# max9611.net
KiCad netlist of a schematic drawn in EAGLE
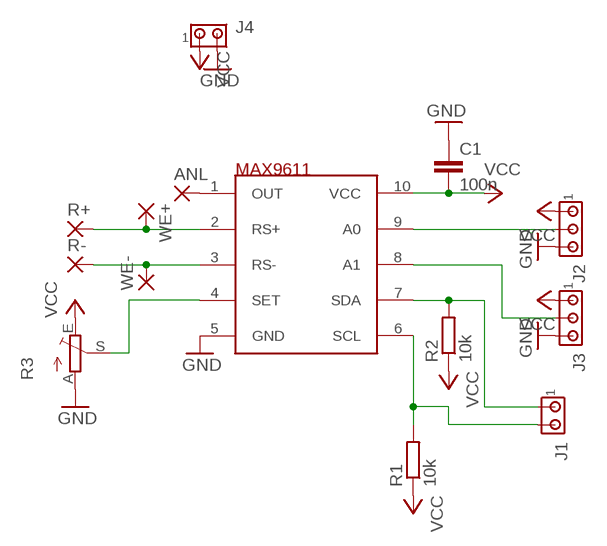
[diagram p0: schematic, sheet 1]

(export (version "E")
  (design (tool "Eeschema 10.0.6"))
  (components
    (comp (ref "ANL")
      (value "1,6/0,8")
      (footprint "eagle-import:1,6_0,8")
      (libsource (lib "eagle-import") (part "1,6/0,8"))
    )
    (comp (ref "C1")
      (value "100n")
      (footprint "eagle-import:C0805")
      (libsource (lib "eagle-import") (part "C-EUC0805"))
    )
    (comp (ref "J1")
      (value "MTA02-100")
      (footprint "eagle-import:10X02MTA")
      (libsource (lib "eagle-import") (part "MTA02-100"))
    )
    (comp (ref "J2")
      (value "MTA03-100")
      (footprint "eagle-import:10X03MTA")
      (libsource (lib "eagle-import") (part "MTA03-100"))
    )
    (comp (ref "J3")
      (value "MTA03-100")
      (footprint "eagle-import:10X03MTA")
      (libsource (lib "eagle-import") (part "MTA03-100"))
    )
    (comp (ref "J4")
      (value "MTA02-100")
      (footprint "eagle-import:10X02MTA")
      (libsource (lib "eagle-import") (part "MTA02-100"))
    )
    (comp (ref "R+")
      (value "1,6/0,8")
      (footprint "eagle-import:1,6_0,8")
      (libsource (lib "eagle-import") (part "1,6/0,8"))
    )
    (comp (ref "R-")
      (value "1,6/0,8")
      (footprint "eagle-import:1,6_0,8")
      (libsource (lib "eagle-import") (part "1,6/0,8"))
    )
    (comp (ref "R1")
      (value "10k")
      (footprint "eagle-import:M0805")
      (libsource (lib "eagle-import") (part "R-EU_M0805"))
    )
    (comp (ref "R2")
      (value "10k")
      (footprint "eagle-import:M0805")
      (libsource (lib "eagle-import") (part "R-EU_M0805"))
    )
    (comp (ref "R3")
      (value "TRIM_EU-RJ9W")
      (footprint "eagle-import:RJ9W")
      (libsource (lib "eagle-import") (part "TRIM_EU-RJ9W"))
    )
    (comp (ref "U$1")
      (value "MAX9611")
      (footprint "eagle-import:UMAX10")
      (libsource (lib "eagle-import") (part "MAX9611"))
    )
    (comp (ref "WE+")
      (value "1,6/0,8")
      (footprint "eagle-import:1,6_0,8")
      (libsource (lib "eagle-import") (part "1,6/0,8"))
    )
    (comp (ref "WE-")
      (value "1,6/0,8")
      (footprint "eagle-import:1,6_0,8")
      (libsource (lib "eagle-import") (part "1,6/0,8"))
    )
  )
  (nets
    (net (code "1") (name "GND") (class "Default")
      (node (ref "C1") (pin "1") (pinfunction "1_1") (pintype "passive"))
      (node (ref "J2") (pin "3") (pinfunction "3_3") (pintype "passive"))
      (node (ref "J3") (pin "3") (pinfunction "3_3") (pintype "passive"))
      (node (ref "J4") (pin "2") (pinfunction "2_2") (pintype "passive"))
      (node (ref "R3") (pin "A") (pinfunction "A_A") (pintype "passive"))
      (node (ref "U$1") (pin "5") (pinfunction "GND_5") (pintype "bidirectional"))
    )
    (net (code "2") (name "Net-(ANL-P)") (class "Default")
      (node (ref "ANL") (pin "1") (pinfunction "P_1") (pintype "passive"))
      (node (ref "U$1") (pin "1") (pinfunction "OUT_1") (pintype "bidirectional"))
    )
    (net (code "3") (name "Net-(R+-P)") (class "Default")
      (node (ref "R+") (pin "1") (pinfunction "P_1") (pintype "passive"))
      (node (ref "U$1") (pin "2") (pinfunction "RS+_2") (pintype "bidirectional"))
      (node (ref "WE+") (pin "1") (pinfunction "P_1") (pintype "passive"))
    )
    (net (code "4") (name "Net-(R--P)") (class "Default")
      (node (ref "R-") (pin "1") (pinfunction "P_1") (pintype "passive"))
      (node (ref "U$1") (pin "3") (pinfunction "RS-_3") (pintype "bidirectional"))
      (node (ref "WE-") (pin "1") (pinfunction "P_1") (pintype "passive"))
    )
    (net (code "5") (name "Net-(U$1-A0)") (class "Default")
      (node (ref "J2") (pin "2") (pinfunction "2_2") (pintype "passive"))
      (node (ref "U$1") (pin "9") (pinfunction "A0_9") (pintype "bidirectional"))
    )
    (net (code "6") (name "Net-(U$1-A1)") (class "Default")
      (node (ref "J3") (pin "2") (pinfunction "2_2") (pintype "passive"))
      (node (ref "U$1") (pin "8") (pinfunction "A1_8") (pintype "bidirectional"))
    )
    (net (code "7") (name "Net-(U$1-SCL)") (class "Default")
      (node (ref "J1") (pin "2") (pinfunction "2_2") (pintype "passive"))
      (node (ref "R1") (pin "2") (pinfunction "2_2") (pintype "passive"))
      (node (ref "U$1") (pin "6") (pinfunction "SCL_6") (pintype "bidirectional"))
    )
    (net (code "8") (name "Net-(U$1-SDA)") (class "Default")
      (node (ref "J1") (pin "1") (pinfunction "1_1") (pintype "passive"))
      (node (ref "R2") (pin "2") (pinfunction "2_2") (pintype "passive"))
      (node (ref "U$1") (pin "7") (pinfunction "SDA_7") (pintype "bidirectional"))
    )
    (net (code "9") (name "Net-(U$1-SET)") (class "Default")
      (node (ref "R3") (pin "S") (pinfunction "S_S") (pintype "passive"))
      (node (ref "U$1") (pin "4") (pinfunction "SET_4") (pintype "bidirectional"))
    )
    (net (code "10") (name "VCC") (class "Default")
      (node (ref "C1") (pin "2") (pinfunction "2_2") (pintype "passive"))
      (node (ref "J2") (pin "1") (pinfunction "1_1") (pintype "passive"))
      (node (ref "J3") (pin "1") (pinfunction "1_1") (pintype "passive"))
      (node (ref "J4") (pin "1") (pinfunction "1_1") (pintype "passive"))
      (node (ref "R1") (pin "1") (pinfunction "1_1") (pintype "passive"))
      (node (ref "R2") (pin "1") (pinfunction "1_1") (pintype "passive"))
      (node (ref "R3") (pin "E") (pinfunction "E_E") (pintype "passive"))
      (node (ref "U$1") (pin "10") (pinfunction "VCC_10") (pintype "bidirectional"))
    )
  )
)
